# receiver.net
KiCad netlist of a schematic drawn in EAGLE
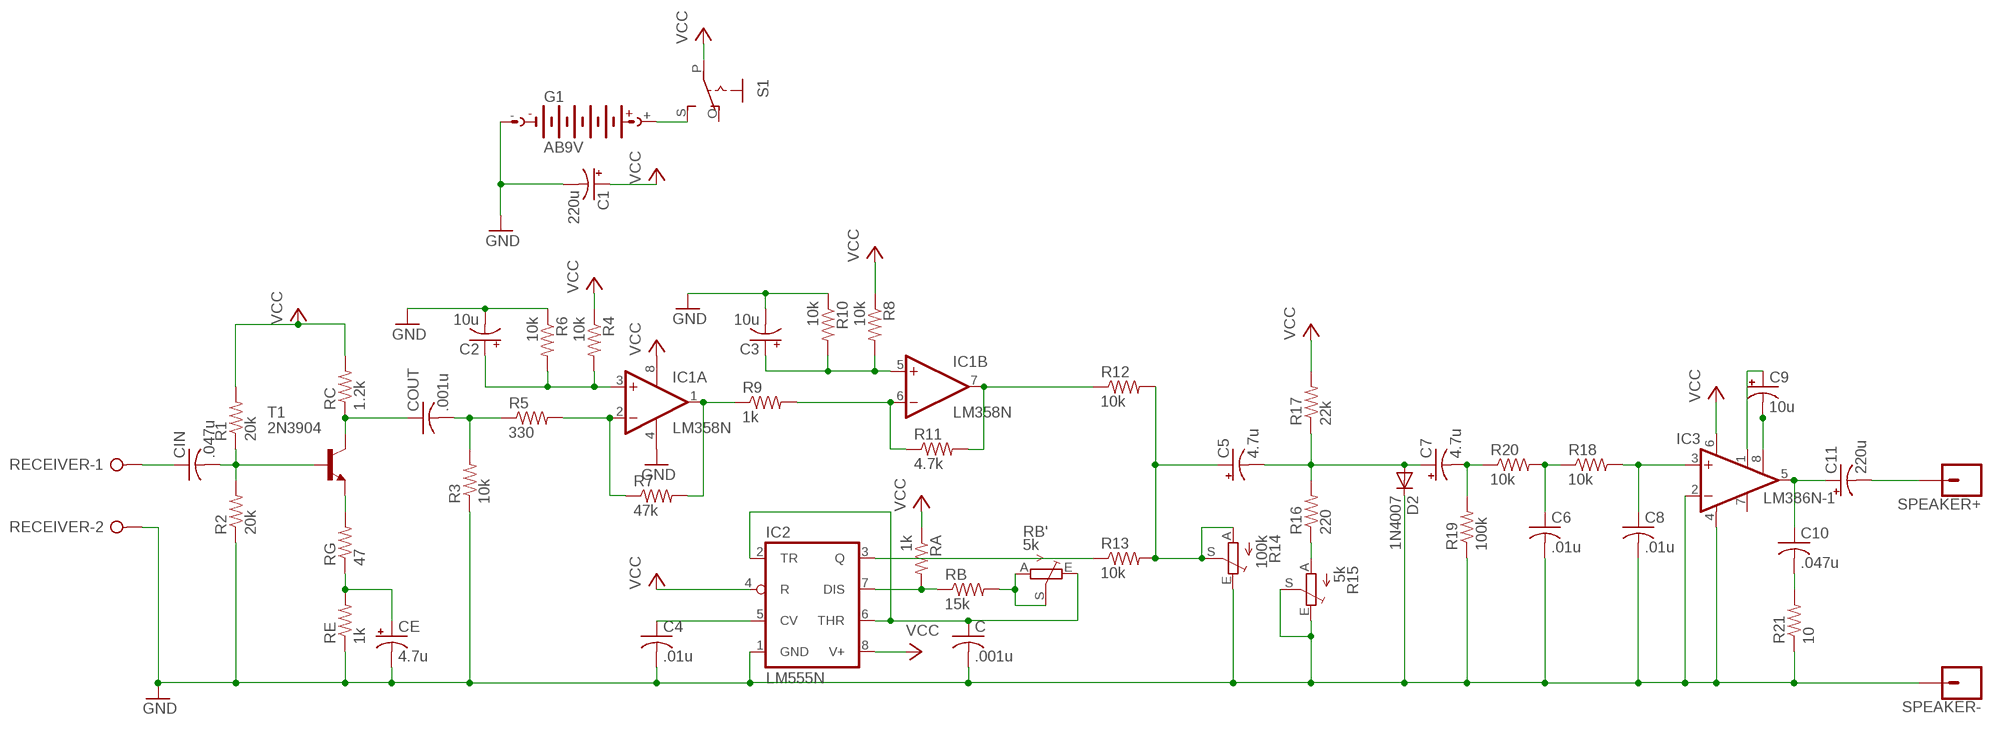
[diagram p0: schematic, sheet 1]

(export (version "E")
  (design (tool "Eeschema 10.0.6"))
  (components
    (comp (ref "C")
      (value ".001u")
      (footprint "eagle-import:C050-024X044")
      (libsource (lib "eagle-import") (part "C-US050-024X044"))
    )
    (comp (ref "C1")
      (value "220u")
      (footprint "eagle-import:B45181B")
      (libsource (lib "eagle-import") (part "CPOL-USB45181B"))
    )
    (comp (ref "C2")
      (value "10u")
      (footprint "eagle-import:B45181B")
      (libsource (lib "eagle-import") (part "CPOL-USB45181B"))
    )
    (comp (ref "C3")
      (value "10u")
      (footprint "eagle-import:B45181B")
      (libsource (lib "eagle-import") (part "CPOL-USB45181B"))
    )
    (comp (ref "C4")
      (value ".01u")
      (footprint "eagle-import:C050-024X044")
      (libsource (lib "eagle-import") (part "C-US050-024X044"))
    )
    (comp (ref "C5")
      (value "4.7u")
      (footprint "eagle-import:B45181B")
      (libsource (lib "eagle-import") (part "CPOL-USB45181B"))
    )
    (comp (ref "C6")
      (value ".01u")
      (footprint "eagle-import:C050-024X044")
      (libsource (lib "eagle-import") (part "C-US050-024X044"))
    )
    (comp (ref "C7")
      (value "4.7u")
      (footprint "eagle-import:B45181B")
      (libsource (lib "eagle-import") (part "CPOL-USB45181B"))
    )
    (comp (ref "C8")
      (value ".01u")
      (footprint "eagle-import:C050-024X044")
      (libsource (lib "eagle-import") (part "C-US050-024X044"))
    )
    (comp (ref "C9")
      (value "10u")
      (footprint "eagle-import:B45181B")
      (libsource (lib "eagle-import") (part "CPOL-USB45181B"))
    )
    (comp (ref "C10")
      (value ".047u")
      (footprint "eagle-import:C050-024X044")
      (libsource (lib "eagle-import") (part "C-US050-024X044"))
    )
    (comp (ref "C11")
      (value "220u")
      (footprint "eagle-import:B45181B")
      (libsource (lib "eagle-import") (part "CPOL-USB45181B"))
    )
    (comp (ref "CE")
      (value "4.7u")
      (footprint "eagle-import:B45181B")
      (libsource (lib "eagle-import") (part "CPOL-USB45181B"))
    )
    (comp (ref "CIN")
      (value ".047u")
      (footprint "eagle-import:C050-024X044")
      (libsource (lib "eagle-import") (part "C-US050-024X044"))
    )
    (comp (ref "COUT")
      (value ".001u")
      (footprint "eagle-import:C050-024X044")
      (libsource (lib "eagle-import") (part "C-US050-024X044"))
    )
    (comp (ref "D2")
      (value "1N4007")
      (footprint "eagle-import:DO41-10")
      (libsource (lib "eagle-import") (part "1N4004"))
    )
    (comp (ref "G1")
      (value "AB9V")
      (footprint "eagle-import:AB9V")
      (libsource (lib "eagle-import") (part "AB9V"))
    )
    (comp (ref "IC1")
      (value "LM358N")
      (footprint "eagle-import:DIL08")
      (libsource (lib "eagle-import") (part "LM358N"))
    )
    (comp (ref "IC2")
      (value "LM555N")
      (footprint "eagle-import:DIL08-ROUND")
      (libsource (lib "eagle-import") (part "555NLM"))
    )
    (comp (ref "IC3")
      (value "LM386N-1")
      (footprint "eagle-import:DIL08")
      (libsource (lib "eagle-import") (part "LM386?-N1"))
    )
    (comp (ref "R1")
      (value "20k")
      (footprint "eagle-import:0207_10")
      (libsource (lib "eagle-import") (part "R-US_0207/10"))
    )
    (comp (ref "R2")
      (value "20k")
      (footprint "eagle-import:0207_10")
      (libsource (lib "eagle-import") (part "R-US_0207/10"))
    )
    (comp (ref "R3")
      (value "10k")
      (footprint "eagle-import:0207_10")
      (libsource (lib "eagle-import") (part "R-US_0207/10"))
    )
    (comp (ref "R4")
      (value "10k")
      (footprint "eagle-import:0207_10")
      (libsource (lib "eagle-import") (part "R-US_0207/10"))
    )
    (comp (ref "R5")
      (value "330")
      (footprint "eagle-import:0207_10")
      (libsource (lib "eagle-import") (part "R-US_0207/10"))
    )
    (comp (ref "R6")
      (value "10k")
      (footprint "eagle-import:0207_10")
      (libsource (lib "eagle-import") (part "R-US_0207/10"))
    )
    (comp (ref "R7")
      (value "47k")
      (footprint "eagle-import:0207_10")
      (libsource (lib "eagle-import") (part "R-US_0207/10"))
    )
    (comp (ref "R8")
      (value "10k")
      (footprint "eagle-import:0207_10")
      (libsource (lib "eagle-import") (part "R-US_0207/10"))
    )
    (comp (ref "R9")
      (value "1k")
      (footprint "eagle-import:0207_10")
      (libsource (lib "eagle-import") (part "R-US_0207/10"))
    )
    (comp (ref "R10")
      (value "10k")
      (footprint "eagle-import:0207_10")
      (libsource (lib "eagle-import") (part "R-US_0207/10"))
    )
    (comp (ref "R11")
      (value "4.7k")
      (footprint "eagle-import:0207_10")
      (libsource (lib "eagle-import") (part "R-US_0207/10"))
    )
    (comp (ref "R12")
      (value "10k")
      (footprint "eagle-import:0207_10")
      (libsource (lib "eagle-import") (part "R-US_0207/10"))
    )
    (comp (ref "R13")
      (value "10k")
      (footprint "eagle-import:0207_10")
      (libsource (lib "eagle-import") (part "R-US_0207/10"))
    )
    (comp (ref "R14")
      (value "100k")
      (footprint "eagle-import:B25P")
      (libsource (lib "eagle-import") (part "TRIM_EU-B25P"))
    )
    (comp (ref "R15")
      (value "5k")
      (footprint "eagle-import:B25P")
      (libsource (lib "eagle-import") (part "TRIM_EU-B25P"))
    )
    (comp (ref "R16")
      (value "220")
      (footprint "eagle-import:0207_10")
      (libsource (lib "eagle-import") (part "R-US_0207/10"))
    )
    (comp (ref "R17")
      (value "22k")
      (footprint "eagle-import:0207_10")
      (libsource (lib "eagle-import") (part "R-US_0207/10"))
    )
    (comp (ref "R18")
      (value "10k")
      (footprint "eagle-import:0207_10")
      (libsource (lib "eagle-import") (part "R-US_0207/10"))
    )
    (comp (ref "R19")
      (value "100k")
      (footprint "eagle-import:0207_10")
      (libsource (lib "eagle-import") (part "R-US_0207/10"))
    )
    (comp (ref "R20")
      (value "10k")
      (footprint "eagle-import:0207_10")
      (libsource (lib "eagle-import") (part "R-US_0207/10"))
    )
    (comp (ref "R21")
      (value "10")
      (footprint "eagle-import:0207_10")
      (libsource (lib "eagle-import") (part "R-US_0207/10"))
    )
    (comp (ref "RA")
      (value "1k")
      (footprint "eagle-import:0207_10")
      (libsource (lib "eagle-import") (part "R-US_0207/10"))
    )
    (comp (ref "RB")
      (value "15k")
      (footprint "eagle-import:0207_10")
      (libsource (lib "eagle-import") (part "R-US_0207/10"))
    )
    (comp (ref "RB'")
      (value "5k")
      (footprint "eagle-import:B25P")
      (libsource (lib "eagle-import") (part "TRIM_EU-B25P"))
    )
    (comp (ref "RC")
      (value "1.2k")
      (footprint "eagle-import:0207_10")
      (libsource (lib "eagle-import") (part "R-US_0207/10"))
    )
    (comp (ref "RE")
      (value "1k")
      (footprint "eagle-import:0207_10")
      (libsource (lib "eagle-import") (part "R-US_0207/10"))
    )
    (comp (ref "RECEIVER")
      (value "W237-02P")
      (footprint "eagle-import:W237-132")
      (libsource (lib "eagle-import") (part "W237-02P"))
    )
    (comp (ref "RG")
      (value "47")
      (footprint "eagle-import:0207_10")
      (libsource (lib "eagle-import") (part "R-US_0207/10"))
    )
    (comp (ref "S1")
      (value "EG1218S")
      (footprint "eagle-import:EG1218")
      (libsource (lib "eagle-import") (part "EG1218S"))
    )
    (comp (ref "SPEAKER+")
      (value "CONN_01")
      (footprint "eagle-import:1X01")
      (libsource (lib "eagle-import") (part "CONN_01"))
    )
    (comp (ref "SPEAKER-")
      (value "CONN_01")
      (footprint "eagle-import:1X01")
      (libsource (lib "eagle-import") (part "CONN_01"))
    )
    (comp (ref "T1")
      (value "2N3904")
      (footprint "eagle-import:TO92")
      (libsource (lib "eagle-import") (part "2N3904"))
    )
  )
  (nets
    (net (code "1") (name "GND") (class "Default")
      (node (ref "C") (pin "2") (pinfunction "2_2") (pintype "passive"))
      (node (ref "C1") (pin "-") (pinfunction "-_-") (pintype "passive"))
      (node (ref "C2") (pin "-") (pinfunction "-_-") (pintype "passive"))
      (node (ref "C3") (pin "-") (pinfunction "-_-") (pintype "passive"))
      (node (ref "C4") (pin "2") (pinfunction "2_2") (pintype "passive"))
      (node (ref "C6") (pin "2") (pinfunction "2_2") (pintype "passive"))
      (node (ref "C8") (pin "2") (pinfunction "2_2") (pintype "passive"))
      (node (ref "CE") (pin "-") (pinfunction "-_-") (pintype "passive"))
      (node (ref "D2") (pin "C") (pinfunction "C_C") (pintype "passive"))
      (node (ref "G1") (pin "-") (pinfunction "-_-") (pintype "passive"))
      (node (ref "IC1") (pin "4") (pinfunction "V-_4") (pintype "power_in"))
      (node (ref "IC2") (pin "1") (pinfunction "GND_1") (pintype "power_in"))
      (node (ref "IC3") (pin "2") (pinfunction "-IN_2") (pintype "input"))
      (node (ref "IC3") (pin "4") (pinfunction "GND_4") (pintype "power_in"))
      (node (ref "R10") (pin "1") (pinfunction "1_1") (pintype "passive"))
      (node (ref "R14") (pin "E") (pinfunction "E_E") (pintype "passive"))
      (node (ref "R15") (pin "E") (pinfunction "E_E") (pintype "passive"))
      (node (ref "R15") (pin "S") (pinfunction "S_S") (pintype "passive"))
      (node (ref "R19") (pin "1") (pinfunction "1_1") (pintype "passive"))
      (node (ref "R2") (pin "1") (pinfunction "1_1") (pintype "passive"))
      (node (ref "R21") (pin "1") (pinfunction "1_1") (pintype "passive"))
      (node (ref "R3") (pin "1") (pinfunction "1_1") (pintype "passive"))
      (node (ref "R6") (pin "1") (pinfunction "1_1") (pintype "passive"))
      (node (ref "RE") (pin "1") (pinfunction "1_1") (pintype "passive"))
      (node (ref "RECEIVER") (pin "2") (pinfunction "KL_2") (pintype "passive"))
      (node (ref "SPEAKER-") (pin "1") (pinfunction "1_1") (pintype "passive"))
    )
    (net (code "2") (name "Net-(C5-Pad+)") (class "Default")
      (node (ref "C5") (pin "+") (pinfunction "+_+") (pintype "passive"))
      (node (ref "R12") (pin "2") (pinfunction "2_2") (pintype "passive"))
      (node (ref "R13") (pin "2") (pinfunction "2_2") (pintype "passive"))
      (node (ref "R14") (pin "A") (pinfunction "A_A") (pintype "passive"))
      (node (ref "R14") (pin "S") (pinfunction "S_S") (pintype "passive"))
    )
    (net (code "3") (name "Net-(C5-Pad-)") (class "Default")
      (node (ref "C5") (pin "-") (pinfunction "-_-") (pintype "passive"))
      (node (ref "C7") (pin "+") (pinfunction "+_+") (pintype "passive"))
      (node (ref "D2") (pin "A") (pinfunction "A_A") (pintype "passive"))
      (node (ref "R16") (pin "2") (pinfunction "2_2") (pintype "passive"))
      (node (ref "R17") (pin "1") (pinfunction "1_1") (pintype "passive"))
    )
    (net (code "4") (name "Net-(C6-Pad1)") (class "Default")
      (node (ref "C6") (pin "1") (pinfunction "1_1") (pintype "passive"))
      (node (ref "R18") (pin "1") (pinfunction "1_1") (pintype "passive"))
      (node (ref "R20") (pin "2") (pinfunction "2_2") (pintype "passive"))
    )
    (net (code "5") (name "Net-(C7-Pad-)") (class "Default")
      (node (ref "C7") (pin "-") (pinfunction "-_-") (pintype "passive"))
      (node (ref "R19") (pin "2") (pinfunction "2_2") (pintype "passive"))
      (node (ref "R20") (pin "1") (pinfunction "1_1") (pintype "passive"))
    )
    (net (code "6") (name "Net-(C9-Pad+)") (class "Default")
      (node (ref "C9") (pin "+") (pinfunction "+_+") (pintype "passive"))
      (node (ref "IC3") (pin "1") (pinfunction "GAIN_1") (pintype "passive"))
    )
    (net (code "7") (name "Net-(C9-Pad-)") (class "Default")
      (node (ref "C9") (pin "-") (pinfunction "-_-") (pintype "passive"))
      (node (ref "IC3") (pin "8") (pinfunction "GAIN_8") (pintype "passive"))
    )
    (net (code "8") (name "Net-(C10-Pad2)") (class "Default")
      (node (ref "C10") (pin "2") (pinfunction "2_2") (pintype "passive"))
      (node (ref "R21") (pin "2") (pinfunction "2_2") (pintype "passive"))
    )
    (net (code "9") (name "Net-(C11-Pad-)") (class "Default")
      (node (ref "C11") (pin "-") (pinfunction "-_-") (pintype "passive"))
      (node (ref "SPEAKER+") (pin "1") (pinfunction "1_1") (pintype "passive"))
    )
    (net (code "10") (name "Net-(CE-Pad+)") (class "Default")
      (node (ref "CE") (pin "+") (pinfunction "+_+") (pintype "passive"))
      (node (ref "RE") (pin "2") (pinfunction "2_2") (pintype "passive"))
      (node (ref "RG") (pin "1") (pinfunction "1_1") (pintype "passive"))
    )
    (net (code "11") (name "Net-(COUT-Pad2)") (class "Default")
      (node (ref "COUT") (pin "2") (pinfunction "2_2") (pintype "passive"))
      (node (ref "R3") (pin "2") (pinfunction "2_2") (pintype "passive"))
      (node (ref "R5") (pin "1") (pinfunction "1_1") (pintype "passive"))
    )
    (net (code "12") (name "Net-(G1-Pad+)") (class "Default")
      (node (ref "G1") (pin "+") (pinfunction "+_+") (pintype "passive"))
      (node (ref "S1") (pin "S") (pinfunction "S_S") (pintype "passive"))
    )
    (net (code "13") (name "Net-(IC1A-+IN)") (class "Default")
      (node (ref "C2") (pin "+") (pinfunction "+_+") (pintype "passive"))
      (node (ref "IC1") (pin "3") (pinfunction "+IN_3") (pintype "input"))
      (node (ref "R4") (pin "2") (pinfunction "2_2") (pintype "passive"))
      (node (ref "R6") (pin "2") (pinfunction "2_2") (pintype "passive"))
    )
    (net (code "14") (name "Net-(IC1A--IN)") (class "Default")
      (node (ref "IC1") (pin "2") (pinfunction "-IN_2") (pintype "input"))
      (node (ref "R5") (pin "2") (pinfunction "2_2") (pintype "passive"))
      (node (ref "R7") (pin "1") (pinfunction "1_1") (pintype "passive"))
    )
    (net (code "15") (name "Net-(IC1A-OUT)") (class "Default")
      (node (ref "IC1") (pin "1") (pinfunction "OUT_1") (pintype "output"))
      (node (ref "R7") (pin "2") (pinfunction "2_2") (pintype "passive"))
      (node (ref "R9") (pin "1") (pinfunction "1_1") (pintype "passive"))
    )
    (net (code "16") (name "Net-(IC1B-+IN)") (class "Default")
      (node (ref "C3") (pin "+") (pinfunction "+_+") (pintype "passive"))
      (node (ref "IC1") (pin "5") (pinfunction "+IN_5") (pintype "input"))
      (node (ref "R10") (pin "2") (pinfunction "2_2") (pintype "passive"))
      (node (ref "R8") (pin "2") (pinfunction "2_2") (pintype "passive"))
    )
    (net (code "17") (name "Net-(IC1B--IN)") (class "Default")
      (node (ref "IC1") (pin "6") (pinfunction "-IN_6") (pintype "input"))
      (node (ref "R11") (pin "1") (pinfunction "1_1") (pintype "passive"))
      (node (ref "R9") (pin "2") (pinfunction "2_2") (pintype "passive"))
    )
    (net (code "18") (name "Net-(IC1B-OUT)") (class "Default")
      (node (ref "IC1") (pin "7") (pinfunction "OUT_7") (pintype "output"))
      (node (ref "R11") (pin "2") (pinfunction "2_2") (pintype "passive"))
      (node (ref "R12") (pin "1") (pinfunction "1_1") (pintype "passive"))
    )
    (net (code "19") (name "Net-(IC2-CV)") (class "Default")
      (node (ref "C4") (pin "1") (pinfunction "1_1") (pintype "passive"))
      (node (ref "IC2") (pin "5") (pinfunction "CV_5") (pintype "input"))
    )
    (net (code "20") (name "Net-(IC2-DIS)") (class "Default")
      (node (ref "IC2") (pin "7") (pinfunction "DIS_7") (pintype "input"))
      (node (ref "RA") (pin "2") (pinfunction "2_2") (pintype "passive"))
      (node (ref "RB") (pin "1") (pinfunction "1_1") (pintype "passive"))
    )
    (net (code "21") (name "Net-(IC2-Q)") (class "Default")
      (node (ref "IC2") (pin "3") (pinfunction "Q_3") (pintype "output"))
      (node (ref "R13") (pin "1") (pinfunction "1_1") (pintype "passive"))
    )
    (net (code "22") (name "Net-(IC2-THR)") (class "Default")
      (node (ref "C") (pin "1") (pinfunction "1_1") (pintype "passive"))
      (node (ref "IC2") (pin "2") (pinfunction "TR_2") (pintype "input"))
      (node (ref "IC2") (pin "6") (pinfunction "THR_6") (pintype "input"))
      (node (ref "RB'") (pin "E") (pinfunction "E_E") (pintype "passive"))
    )
    (net (code "23") (name "Net-(IC3-+IN)") (class "Default")
      (node (ref "C8") (pin "1") (pinfunction "1_1") (pintype "passive"))
      (node (ref "IC3") (pin "3") (pinfunction "+IN_3") (pintype "input"))
      (node (ref "R18") (pin "2") (pinfunction "2_2") (pintype "passive"))
    )
    (net (code "24") (name "Net-(IC3-OUT)") (class "Default")
      (node (ref "C10") (pin "1") (pinfunction "1_1") (pintype "passive"))
      (node (ref "C11") (pin "+") (pinfunction "+_+") (pintype "passive"))
      (node (ref "IC3") (pin "5") (pinfunction "OUT_5") (pintype "output"))
    )
    (net (code "25") (name "Net-(R15-PadA)") (class "Default")
      (node (ref "R15") (pin "A") (pinfunction "A_A") (pintype "passive"))
      (node (ref "R16") (pin "1") (pinfunction "1_1") (pintype "passive"))
    )
    (net (code "26") (name "Net-(RB'-PadA)") (class "Default")
      (node (ref "RB") (pin "2") (pinfunction "2_2") (pintype "passive"))
      (node (ref "RB'") (pin "A") (pinfunction "A_A") (pintype "passive"))
      (node (ref "RB'") (pin "S") (pinfunction "S_S") (pintype "passive"))
    )
    (net (code "27") (name "Net-(RECEIVERA-KL)") (class "Default")
      (node (ref "CIN") (pin "1") (pinfunction "1_1") (pintype "passive"))
      (node (ref "RECEIVER") (pin "1") (pinfunction "KL_1") (pintype "passive"))
    )
    (net (code "28") (name "Net-(T1-B)") (class "Default")
      (node (ref "CIN") (pin "2") (pinfunction "2_2") (pintype "passive"))
      (node (ref "R1") (pin "1") (pinfunction "1_1") (pintype "passive"))
      (node (ref "R2") (pin "2") (pinfunction "2_2") (pintype "passive"))
      (node (ref "T1") (pin "2") (pinfunction "B_2") (pintype "passive"))
    )
    (net (code "29") (name "Net-(T1-C)") (class "Default")
      (node (ref "COUT") (pin "1") (pinfunction "1_1") (pintype "passive"))
      (node (ref "RC") (pin "1") (pinfunction "1_1") (pintype "passive"))
      (node (ref "T1") (pin "1") (pinfunction "C_1") (pintype "passive"))
    )
    (net (code "30") (name "Net-(T1-E)") (class "Default")
      (node (ref "RG") (pin "2") (pinfunction "2_2") (pintype "passive"))
      (node (ref "T1") (pin "3") (pinfunction "E_3") (pintype "passive"))
    )
    (net (code "31") (name "VCC") (class "Default")
      (node (ref "C1") (pin "+") (pinfunction "+_+") (pintype "passive"))
      (node (ref "IC1") (pin "8") (pinfunction "V+_8") (pintype "power_in"))
      (node (ref "IC2") (pin "4") (pinfunction "R_4") (pintype "input"))
      (node (ref "IC2") (pin "8") (pinfunction "V+_8") (pintype "power_in"))
      (node (ref "IC3") (pin "6") (pinfunction "VS_6") (pintype "power_in"))
      (node (ref "R1") (pin "2") (pinfunction "2_2") (pintype "passive"))
      (node (ref "R17") (pin "2") (pinfunction "2_2") (pintype "passive"))
      (node (ref "R4") (pin "1") (pinfunction "1_1") (pintype "passive"))
      (node (ref "R8") (pin "1") (pinfunction "1_1") (pintype "passive"))
      (node (ref "RA") (pin "1") (pinfunction "1_1") (pintype "passive"))
      (node (ref "RC") (pin "2") (pinfunction "2_2") (pintype "passive"))
      (node (ref "S1") (pin "P") (pinfunction "P_P") (pintype "passive"))
    )
    (net (code "32") (name "unconnected-(IC3-BYPASS-Pad7)") (class "Default")
      (node (ref "IC3") (pin "7") (pinfunction "BYPASS_7") (pintype "passive"))
    )
    (net (code "33") (name "unconnected-(S1-PadO)") (class "Default")
      (node (ref "S1") (pin "O") (pinfunction "O_O") (pintype "passive"))
    )
  )
)
